# Proiect_OpenBook_V2_v1.net
KiCad netlist of a schematic drawn in EAGLE
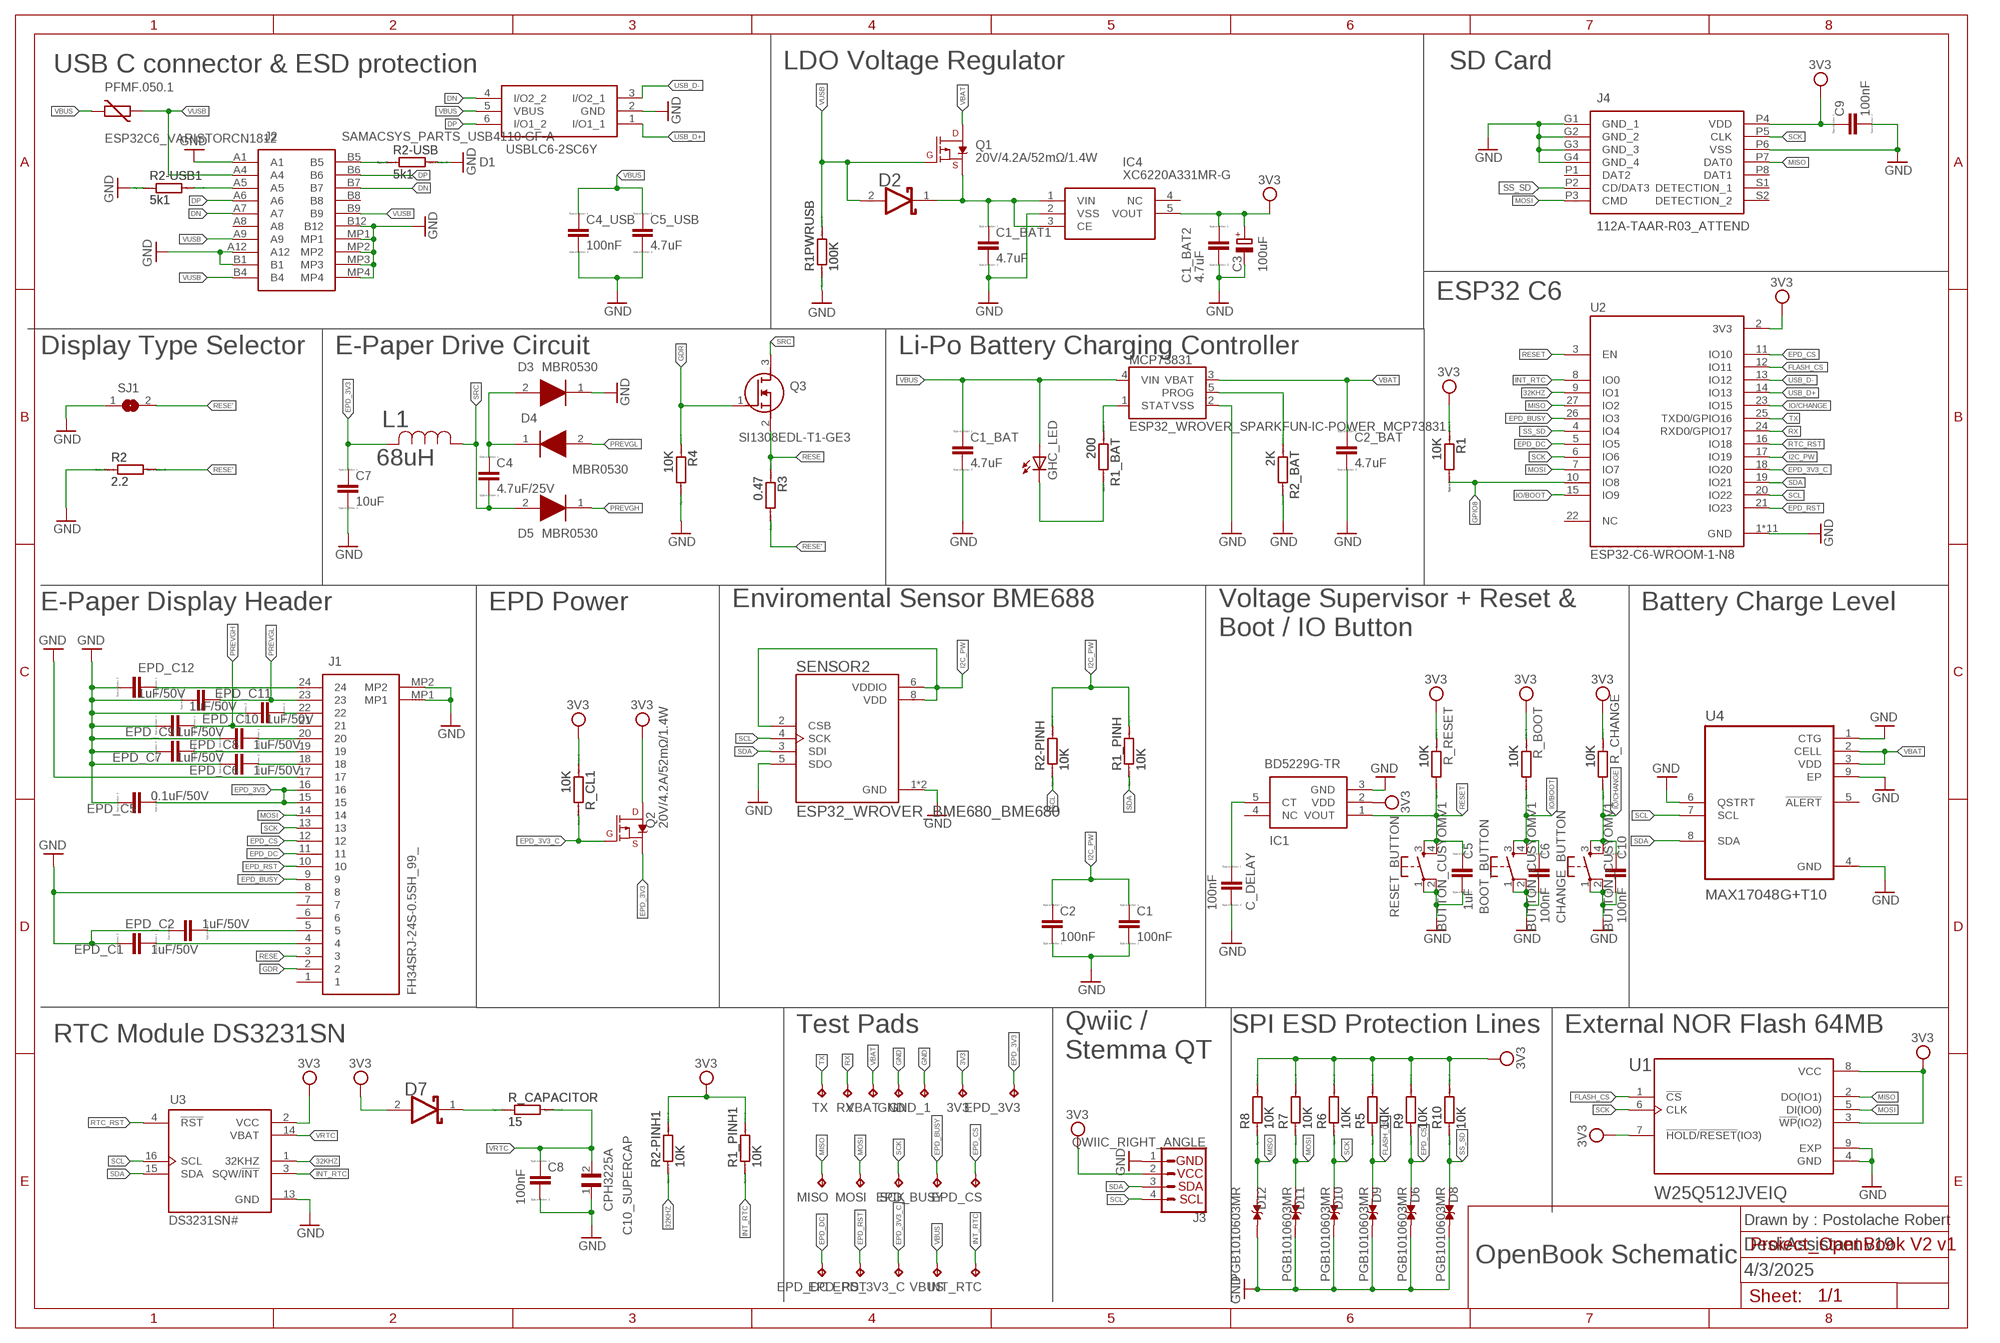
[diagram p0: schematic, sheet 1]

(export (version "E")
  (design (tool "Eeschema 10.0.6"))
  (components
    (comp (ref "3V3")
      (value "TPTP20R")
      (footprint "eagle-import:TP20R")
      (libsource (lib "eagle-import") (part "TPTP20R"))
    )
    (comp (ref "BOOT_BUTTON")
      (value "BUTTON_CUSYOMV1")
      (footprint "eagle-import:MYBUTTON")
      (libsource (lib "eagle-import") (part "BUTTON_CUSYOMV1"))
    )
    (comp (ref "C1")
      (value "100nF")
      (footprint "eagle-import:ESP32_WROVER_EAGLE-LTSPICE_C0402")
      (libsource (lib "eagle-import") (part "EAGLE-LTSPICE_CC0402"))
    )
    (comp (ref "C1_BAT")
      (value "4.7uF")
      (footprint "eagle-import:ESP32_WROVER_EAGLE-LTSPICE_C0402")
      (libsource (lib "eagle-import") (part "EAGLE-LTSPICE_CC0402"))
    )
    (comp (ref "C1_BAT1")
      (value "4.7uF")
      (footprint "eagle-import:ESP32_WROVER_EAGLE-LTSPICE_C0402")
      (libsource (lib "eagle-import") (part "EAGLE-LTSPICE_CC0402"))
    )
    (comp (ref "C1_BAT2")
      (value "4.7uF")
      (footprint "eagle-import:ESP32_WROVER_EAGLE-LTSPICE_C0402")
      (libsource (lib "eagle-import") (part "EAGLE-LTSPICE_CC0402"))
    )
    (comp (ref "C2")
      (value "100nF")
      (footprint "eagle-import:ESP32_WROVER_EAGLE-LTSPICE_C0402")
      (libsource (lib "eagle-import") (part "EAGLE-LTSPICE_CC0402"))
    )
    (comp (ref "C2_BAT")
      (value "4.7uF")
      (footprint "eagle-import:ESP32_WROVER_EAGLE-LTSPICE_C0402")
      (libsource (lib "eagle-import") (part "EAGLE-LTSPICE_CC0402"))
    )
    (comp (ref "C3")
      (value "100uF")
      (footprint "eagle-import:RCL_CT3528")
      (libsource (lib "eagle-import") (part "RCL_CPOL-EUCT3528"))
    )
    (comp (ref "C4")
      (value "4.7uF/25V")
      (footprint "eagle-import:ESP32_WROVER_EAGLE-LTSPICE_C0402")
      (libsource (lib "eagle-import") (part "EAGLE-LTSPICE_CC0402"))
    )
    (comp (ref "C4_USB")
      (value "100nF")
      (footprint "eagle-import:ESP32_WROVER_EAGLE-LTSPICE_C0402")
      (libsource (lib "eagle-import") (part "EAGLE-LTSPICE_CC0402"))
    )
    (comp (ref "C5")
      (value "1uF")
      (footprint "eagle-import:ESP32_WROVER_EAGLE-LTSPICE_C0402")
      (libsource (lib "eagle-import") (part "EAGLE-LTSPICE_CC0402"))
    )
    (comp (ref "C5_USB")
      (value "4.7uF")
      (footprint "eagle-import:ESP32_WROVER_EAGLE-LTSPICE_C0402")
      (libsource (lib "eagle-import") (part "EAGLE-LTSPICE_CC0402"))
    )
    (comp (ref "C6")
      (value "100nF")
      (footprint "eagle-import:ESP32_WROVER_EAGLE-LTSPICE_C0402")
      (libsource (lib "eagle-import") (part "EAGLE-LTSPICE_CC0402"))
    )
    (comp (ref "C7")
      (value "10uF")
      (footprint "eagle-import:ESP32_WROVER_EAGLE-LTSPICE_C0402")
      (libsource (lib "eagle-import") (part "EAGLE-LTSPICE_CC0402"))
    )
    (comp (ref "C8")
      (value "100nF")
      (footprint "eagle-import:ESP32_WROVER_EAGLE-LTSPICE_C0402")
      (libsource (lib "eagle-import") (part "EAGLE-LTSPICE_CC0402"))
    )
    (comp (ref "C9")
      (value "100nF")
      (footprint "eagle-import:ESP32_WROVER_EAGLE-LTSPICE_C0402")
      (libsource (lib "eagle-import") (part "EAGLE-LTSPICE_CC0402"))
    )
    (comp (ref "C10")
      (value "100nF")
      (footprint "eagle-import:ESP32_WROVER_EAGLE-LTSPICE_C0402")
      (libsource (lib "eagle-import") (part "EAGLE-LTSPICE_CC0402"))
    )
    (comp (ref "C10_SUPERCAP")
      (value "CPH3225A")
      (footprint "eagle-import:CAPCP3225X100N")
      (fields (field (name "MF") "Seiko Instruments"))
      (libsource (lib "eagle-import") (part "CPH3225A"))
    )
    (comp (ref "CHANGE_BUTTON")
      (value "BUTTON_CUSYOMV1")
      (footprint "eagle-import:MYBUTTON")
      (libsource (lib "eagle-import") (part "BUTTON_CUSYOMV1"))
    )
    (comp (ref "C_DELAY")
      (value "100nF")
      (footprint "eagle-import:ESP32_WROVER_EAGLE-LTSPICE_C0402")
      (libsource (lib "eagle-import") (part "EAGLE-LTSPICE_CC0402"))
    )
    (comp (ref "D1")
      (value "USBLC6-2SC6Y")
      (footprint "eagle-import:SOT95P280X145-6N")
      (fields (field (name "MF") "STMicroelectronics"))
      (libsource (lib "eagle-import") (part "USBLC6-2SC6Y"))
    )
    (comp (ref "D2")
      (value "ESP32_WROVER_AVX---SD0805S020S1R0_AVX_SD0805S020S1R0_0_0AVX_SD0805S020S1R0_0_0")
      (footprint "eagle-import:ESP32_WROVER_AVX---SD0805S020S1R0_AVX_SD0805S020S1R0_0")
      (fields
        (field (name "DIGIKEY_PART_NUMBER") "478-7800-1-ND")
        (field (name "MF") "AVX")
        (field (name "MOUSER_PART_NUMBER") "581-SD0805S020S1R0")
      )
      (libsource (lib "eagle-import") (part "ESP32_WROVER_AVX---SD0805S020S1R0_AVX_SD0805S020S1R0_0_0AVX_SD0805S020S1R0_0_0"))
    )
    (comp (ref "D3")
      (value "MBR0530")
      (footprint "eagle-import:SOD3716X135N")
      (fields (field (name "MF") "ON Semiconductor"))
      (libsource (lib "eagle-import") (part "MBR0530"))
    )
    (comp (ref "D4")
      (value "MBR0530")
      (footprint "eagle-import:SOD3716X135N")
      (fields (field (name "MF") "ON Semiconductor"))
      (libsource (lib "eagle-import") (part "MBR0530"))
    )
    (comp (ref "D5")
      (value "MBR0530")
      (footprint "eagle-import:SOD3716X135N")
      (fields (field (name "MF") "ON Semiconductor"))
      (libsource (lib "eagle-import") (part "MBR0530"))
    )
    (comp (ref "D6")
      (value "PGB1010603MR")
      (footprint "eagle-import:DIOC1608X36N")
      (fields (field (name "MF") "Littelfuse Inc."))
      (libsource (lib "eagle-import") (part "PGB1010603MR"))
    )
    (comp (ref "D7")
      (value "ESP32_WROVER_AVX---SD0805S020S1R0_AVX_SD0805S020S1R0_0_0AVX_SD0805S020S1R0_0_0")
      (footprint "eagle-import:ESP32_WROVER_AVX---SD0805S020S1R0_AVX_SD0805S020S1R0_0")
      (fields
        (field (name "DIGIKEY_PART_NUMBER") "478-7800-1-ND")
        (field (name "MF") "AVX")
        (field (name "MOUSER_PART_NUMBER") "581-SD0805S020S1R0")
      )
      (libsource (lib "eagle-import") (part "ESP32_WROVER_AVX---SD0805S020S1R0_AVX_SD0805S020S1R0_0_0AVX_SD0805S020S1R0_0_0"))
    )
    (comp (ref "D8")
      (value "PGB1010603MR")
      (footprint "eagle-import:DIOC1608X36N")
      (fields (field (name "MF") "Littelfuse Inc."))
      (libsource (lib "eagle-import") (part "PGB1010603MR"))
    )
    (comp (ref "D9")
      (value "PGB1010603MR")
      (footprint "eagle-import:DIOC1608X36N")
      (fields (field (name "MF") "Littelfuse Inc."))
      (libsource (lib "eagle-import") (part "PGB1010603MR"))
    )
    (comp (ref "D10")
      (value "PGB1010603MR")
      (footprint "eagle-import:DIOC1608X36N")
      (fields (field (name "MF") "Littelfuse Inc."))
      (libsource (lib "eagle-import") (part "PGB1010603MR"))
    )
    (comp (ref "D11")
      (value "PGB1010603MR")
      (footprint "eagle-import:DIOC1608X36N")
      (fields (field (name "MF") "Littelfuse Inc."))
      (libsource (lib "eagle-import") (part "PGB1010603MR"))
    )
    (comp (ref "D12")
      (value "PGB1010603MR")
      (footprint "eagle-import:DIOC1608X36N")
      (fields (field (name "MF") "Littelfuse Inc."))
      (libsource (lib "eagle-import") (part "PGB1010603MR"))
    )
    (comp (ref "EPD_3V3")
      (value "TPTP20R")
      (footprint "eagle-import:TP20R")
      (libsource (lib "eagle-import") (part "TPTP20R"))
    )
    (comp (ref "EPD_3V3_C")
      (value "TPTP20R")
      (footprint "eagle-import:TP20R")
      (libsource (lib "eagle-import") (part "TPTP20R"))
    )
    (comp (ref "EPD_BUSY")
      (value "TPTP20R")
      (footprint "eagle-import:TP20R")
      (libsource (lib "eagle-import") (part "TPTP20R"))
    )
    (comp (ref "EPD_C1")
      (value "1uF/50V")
      (footprint "eagle-import:ESP32_WROVER_EAGLE-LTSPICE_C0402")
      (libsource (lib "eagle-import") (part "EAGLE-LTSPICE_CC0402"))
    )
    (comp (ref "EPD_C2")
      (value "1uF/50V")
      (footprint "eagle-import:ESP32_WROVER_EAGLE-LTSPICE_C0402")
      (libsource (lib "eagle-import") (part "EAGLE-LTSPICE_CC0402"))
    )
    (comp (ref "EPD_C5")
      (value "0.1uF/50V")
      (footprint "eagle-import:ESP32_WROVER_EAGLE-LTSPICE_C0402")
      (libsource (lib "eagle-import") (part "EAGLE-LTSPICE_CC0402"))
    )
    (comp (ref "EPD_C6")
      (value "1uF/50V")
      (footprint "eagle-import:ESP32_WROVER_EAGLE-LTSPICE_C0402")
      (libsource (lib "eagle-import") (part "EAGLE-LTSPICE_CC0402"))
    )
    (comp (ref "EPD_C7")
      (value "1uF/50V")
      (footprint "eagle-import:ESP32_WROVER_EAGLE-LTSPICE_C0402")
      (libsource (lib "eagle-import") (part "EAGLE-LTSPICE_CC0402"))
    )
    (comp (ref "EPD_C8")
      (value "1uF/50V")
      (footprint "eagle-import:ESP32_WROVER_EAGLE-LTSPICE_C0402")
      (libsource (lib "eagle-import") (part "EAGLE-LTSPICE_CC0402"))
    )
    (comp (ref "EPD_C9")
      (value "1uF/50V")
      (footprint "eagle-import:ESP32_WROVER_EAGLE-LTSPICE_C0402")
      (libsource (lib "eagle-import") (part "EAGLE-LTSPICE_CC0402"))
    )
    (comp (ref "EPD_C10")
      (value "1uF/50V")
      (footprint "eagle-import:ESP32_WROVER_EAGLE-LTSPICE_C0402")
      (libsource (lib "eagle-import") (part "EAGLE-LTSPICE_CC0402"))
    )
    (comp (ref "EPD_C11")
      (value "1uF/50V")
      (footprint "eagle-import:ESP32_WROVER_EAGLE-LTSPICE_C0402")
      (libsource (lib "eagle-import") (part "EAGLE-LTSPICE_CC0402"))
    )
    (comp (ref "EPD_C12")
      (value "1uF/50V")
      (footprint "eagle-import:ESP32_WROVER_EAGLE-LTSPICE_C0402")
      (libsource (lib "eagle-import") (part "EAGLE-LTSPICE_CC0402"))
    )
    (comp (ref "EPD_CS")
      (value "TPTP20R")
      (footprint "eagle-import:TP20R")
      (libsource (lib "eagle-import") (part "TPTP20R"))
    )
    (comp (ref "EPD_DC")
      (value "TPTP20R")
      (footprint "eagle-import:TP20R")
      (libsource (lib "eagle-import") (part "TPTP20R"))
    )
    (comp (ref "EPD_RST")
      (value "TPTP20R")
      (footprint "eagle-import:TP20R")
      (libsource (lib "eagle-import") (part "TPTP20R"))
    )
    (comp (ref "GHC_LED")
      (value "ADAFRUIT_LEDCHIP-LED0603")
      (footprint "eagle-import:ADAFRUIT_CHIP-LED0603")
      (libsource (lib "eagle-import") (part "ADAFRUIT_LEDCHIP-LED0603"))
    )
    (comp (ref "GND")
      (value "TPTP20R")
      (footprint "eagle-import:TP20R")
      (libsource (lib "eagle-import") (part "TPTP20R"))
    )
    (comp (ref "GND_1")
      (value "TPTP20R")
      (footprint "eagle-import:TP20R")
      (libsource (lib "eagle-import") (part "TPTP20R"))
    )
    (comp (ref "IC1")
      (value "BD5229G-TR")
      (footprint "eagle-import:SOT95P280X125-5N")
      (fields (field (name "MOUSER_PART_NUMBER") "755-BD5229G-TR"))
      (libsource (lib "eagle-import") (part "BD5229G-TR"))
    )
    (comp (ref "IC4")
      (value "XC6220A331MR-G")
      (footprint "eagle-import:SOT95P280X120-5N")
      (fields (field (name "MOUSER_PART_NUMBER") "865-XC6220A331MR-G"))
      (libsource (lib "eagle-import") (part "XC6220A331MR-G"))
    )
    (comp (ref "INT_RTC")
      (value "TPTP20R")
      (footprint "eagle-import:TP20R")
      (libsource (lib "eagle-import") (part "TPTP20R"))
    )
    (comp (ref "J1")
      (value "FH34SRJ-24S-0.5SH_99_")
      (footprint "eagle-import:FH34SRJ24S05SH99")
      (fields
        (field (name "MANUFACTURER_PART_NUMBER") "FH34SRJ-24S-0.5SH(99)")
        (field (name "MOUSER_PART_NUMBER") "798-FH34SRJ24S05SH99")
      )
      (libsource (lib "eagle-import") (part "FH34SRJ-24S-0.5SH_99_"))
    )
    (comp (ref "J2")
      (value "SAMACSYS_PARTS_USB4110-GF-A")
      (footprint "eagle-import:SAMACSYS_PARTS_USB4110GFA")
      (fields
        (field (name "MANUFACTURER_PART_NUMBER") "USB4110-GF-A")
        (field (name "MOUSER_PART_NUMBER") "640-USB4110-GF-A")
      )
      (libsource (lib "eagle-import") (part "SAMACSYS_PARTS_USB4110-GF-A"))
    )
    (comp (ref "J3")
      (value "QWIIC_RIGHT_ANGLE")
      (footprint "eagle-import:JST04_1MM_RA")
      (libsource (lib "eagle-import") (part "QWIIC_CONNECTORJS-1MM"))
    )
    (comp (ref "J4")
      (value "112A-TAAR-R03_ATTEND")
      (footprint "eagle-import:112ATAARR03ATTEND")
      (fields (field (name "MANUFACTURER_PART_NUMBER") "112A-TAAR-R03 ATTEND"))
      (libsource (lib "eagle-import") (part "112A-TAAR-R03_ATTEND"))
    )
    (comp (ref "L1")
      (value "68uH")
      (footprint "eagle-import:IND_4828-WE-TPC_WRE")
      (fields
        (field (name "MANUFACTURER_PART_NUMBER") "744043680")
        (field (name "COPYRIGHT") "Copyright (C) 2024 Ultra Librarian. All rights reserved.")
      )
      (libsource (lib "eagle-import") (part "744043680IND_4828-WE-TPC_WRE"))
    )
    (comp (ref "MCP73831")
      (value "ESP32_WROVER_SPARKFUN-IC-POWER_MCP73831")
      (footprint "eagle-import:ESP32_WROVER_SPARKFUN-IC-POWER_SOT23-5")
      (libsource (lib "eagle-import") (part "ESP32_WROVER_SPARKFUN-IC-POWER_MCP73831"))
    )
    (comp (ref "MISO")
      (value "TPTP20R")
      (footprint "eagle-import:TP20R")
      (libsource (lib "eagle-import") (part "TPTP20R"))
    )
    (comp (ref "MOSI")
      (value "TPTP20R")
      (footprint "eagle-import:TP20R")
      (libsource (lib "eagle-import") (part "TPTP20R"))
    )
    (comp (ref "PFMF.050.1")
      (value "ESP32C6_VARISTORCN1812")
      (footprint "eagle-import:ESP32C6_VARISTOR_CT_CN1812")
      (libsource (lib "eagle-import") (part "ESP32C6_VARISTORCN1812"))
    )
    (comp (ref "Q1")
      (value "20V/4.2A/52mΩ/1.4W")
      (footprint "eagle-import:ESP32_WROVER_SPARKFUN-DISCRETESEMI_SOT23-3")
      (libsource (lib "eagle-import") (part "ESP32_WROVER_SPARKFUN-DISCRETESEMI_MOSFET_PCH-DMG2305UX-7"))
    )
    (comp (ref "Q2")
      (value "20V/4.2A/52mΩ/1.4W")
      (footprint "eagle-import:ESP32_WROVER_SPARKFUN-DISCRETESEMI_SOT23-3")
      (libsource (lib "eagle-import") (part "ESP32_WROVER_SPARKFUN-DISCRETESEMI_MOSFET_PCH-DMG2305UX-7"))
    )
    (comp (ref "Q3")
      (value "SI1308EDL-T1-GE3")
      (footprint "eagle-import:SOT65P210X110-3N")
      (fields (field (name "MF") "Vishay Siliconix"))
      (libsource (lib "eagle-import") (part "SI1308EDL-T1-GE3"))
    )
    (comp (ref "R1")
      (value "10K")
      (footprint "eagle-import:ESP32_WROVER_EAGLE-LTSPICE_R0402")
      (libsource (lib "eagle-import") (part "ESP32_WROVER_EAGLE-LTSPICE_RR0402"))
    )
    (comp (ref "R1PWRUSB")
      (value "100K")
      (footprint "eagle-import:ESP32_WROVER_EAGLE-LTSPICE_R0402")
      (libsource (lib "eagle-import") (part "ESP32_WROVER_EAGLE-LTSPICE_RR0402"))
    )
    (comp (ref "R1_BAT")
      (value "200")
      (footprint "eagle-import:ESP32_WROVER_EAGLE-LTSPICE_R0402")
      (libsource (lib "eagle-import") (part "ESP32_WROVER_EAGLE-LTSPICE_RR0402"))
    )
    (comp (ref "R1_PINH")
      (value "10K")
      (footprint "eagle-import:ESP32_WROVER_EAGLE-LTSPICE_R0402")
      (libsource (lib "eagle-import") (part "ESP32_WROVER_EAGLE-LTSPICE_RR0402"))
    )
    (comp (ref "R1_PINH1")
      (value "10K")
      (footprint "eagle-import:ESP32_WROVER_EAGLE-LTSPICE_R0402")
      (libsource (lib "eagle-import") (part "ESP32_WROVER_EAGLE-LTSPICE_RR0402"))
    )
    (comp (ref "R2")
      (value "2.2")
      (footprint "eagle-import:ESP32_WROVER_EAGLE-LTSPICE_R0402")
      (libsource (lib "eagle-import") (part "ESP32_WROVER_EAGLE-LTSPICE_RR0402"))
    )
    (comp (ref "R2-PINH")
      (value "10K")
      (footprint "eagle-import:ESP32_WROVER_EAGLE-LTSPICE_R0402")
      (libsource (lib "eagle-import") (part "ESP32_WROVER_EAGLE-LTSPICE_RR0402"))
    )
    (comp (ref "R2-PINH1")
      (value "10K")
      (footprint "eagle-import:ESP32_WROVER_EAGLE-LTSPICE_R0402")
      (libsource (lib "eagle-import") (part "ESP32_WROVER_EAGLE-LTSPICE_RR0402"))
    )
    (comp (ref "R2-USB")
      (value "5k1")
      (footprint "eagle-import:ESP32_WROVER_EAGLE-LTSPICE_R0402")
      (libsource (lib "eagle-import") (part "ESP32_WROVER_EAGLE-LTSPICE_RR0402"))
    )
    (comp (ref "R2-USB1")
      (value "5k1")
      (footprint "eagle-import:ESP32_WROVER_EAGLE-LTSPICE_R0402")
      (libsource (lib "eagle-import") (part "ESP32_WROVER_EAGLE-LTSPICE_RR0402"))
    )
    (comp (ref "R2_BAT")
      (value "2K")
      (footprint "eagle-import:ESP32_WROVER_EAGLE-LTSPICE_R0402")
      (libsource (lib "eagle-import") (part "ESP32_WROVER_EAGLE-LTSPICE_RR0402"))
    )
    (comp (ref "R3")
      (value "0.47")
      (footprint "eagle-import:ESP32_WROVER_EAGLE-LTSPICE_R0402")
      (libsource (lib "eagle-import") (part "ESP32_WROVER_EAGLE-LTSPICE_RR0402"))
    )
    (comp (ref "R4")
      (value "10K")
      (footprint "eagle-import:ESP32_WROVER_EAGLE-LTSPICE_R0402")
      (libsource (lib "eagle-import") (part "ESP32_WROVER_EAGLE-LTSPICE_RR0402"))
    )
    (comp (ref "R5")
      (value "10K")
      (footprint "eagle-import:ESP32_WROVER_EAGLE-LTSPICE_R0402")
      (libsource (lib "eagle-import") (part "ESP32_WROVER_EAGLE-LTSPICE_RR0402"))
    )
    (comp (ref "R6")
      (value "10K")
      (footprint "eagle-import:ESP32_WROVER_EAGLE-LTSPICE_R0402")
      (libsource (lib "eagle-import") (part "ESP32_WROVER_EAGLE-LTSPICE_RR0402"))
    )
    (comp (ref "R7")
      (value "10K")
      (footprint "eagle-import:ESP32_WROVER_EAGLE-LTSPICE_R0402")
      (libsource (lib "eagle-import") (part "ESP32_WROVER_EAGLE-LTSPICE_RR0402"))
    )
    (comp (ref "R8")
      (value "10K")
      (footprint "eagle-import:ESP32_WROVER_EAGLE-LTSPICE_R0402")
      (libsource (lib "eagle-import") (part "ESP32_WROVER_EAGLE-LTSPICE_RR0402"))
    )
    (comp (ref "R9")
      (value "10K")
      (footprint "eagle-import:ESP32_WROVER_EAGLE-LTSPICE_R0402")
      (libsource (lib "eagle-import") (part "ESP32_WROVER_EAGLE-LTSPICE_RR0402"))
    )
    (comp (ref "R10")
      (value "10K")
      (footprint "eagle-import:ESP32_WROVER_EAGLE-LTSPICE_R0402")
      (libsource (lib "eagle-import") (part "ESP32_WROVER_EAGLE-LTSPICE_RR0402"))
    )
    (comp (ref "RESET_BUTTON")
      (value "BUTTON_CUSYOMV1")
      (footprint "eagle-import:MYBUTTON")
      (libsource (lib "eagle-import") (part "BUTTON_CUSYOMV1"))
    )
    (comp (ref "RX")
      (value "TPTP20R")
      (footprint "eagle-import:TP20R")
      (libsource (lib "eagle-import") (part "TPTP20R"))
    )
    (comp (ref "R_BOOT")
      (value "10K")
      (footprint "eagle-import:ESP32_WROVER_EAGLE-LTSPICE_R0402")
      (libsource (lib "eagle-import") (part "ESP32_WROVER_EAGLE-LTSPICE_RR0402"))
    )
    (comp (ref "R_CAPACITOR")
      (value "15")
      (footprint "eagle-import:ESP32_WROVER_EAGLE-LTSPICE_R0402")
      (libsource (lib "eagle-import") (part "ESP32_WROVER_EAGLE-LTSPICE_RR0402"))
    )
    (comp (ref "R_CHANGE")
      (value "10K")
      (footprint "eagle-import:ESP32_WROVER_EAGLE-LTSPICE_R0402")
      (libsource (lib "eagle-import") (part "ESP32_WROVER_EAGLE-LTSPICE_RR0402"))
    )
    (comp (ref "R_CL1")
      (value "10K")
      (footprint "eagle-import:ESP32_WROVER_EAGLE-LTSPICE_R0402")
      (libsource (lib "eagle-import") (part "ESP32_WROVER_EAGLE-LTSPICE_RR0402"))
    )
    (comp (ref "R_RESET")
      (value "10K")
      (footprint "eagle-import:ESP32_WROVER_EAGLE-LTSPICE_R0402")
      (libsource (lib "eagle-import") (part "ESP32_WROVER_EAGLE-LTSPICE_RR0402"))
    )
    (comp (ref "SCK")
      (value "TPTP20R")
      (footprint "eagle-import:TP20R")
      (libsource (lib "eagle-import") (part "TPTP20R"))
    )
    (comp (ref "SENSOR2")
      (value "ESP32_WROVER_BME680_BME680")
      (footprint "eagle-import:ESP32_WROVER_BME680_PSON80P300X300X100-8N")
      (fields (field (name "MF") "Bosch Sensortec") (field (name "MP") "BME680"))
      (libsource (lib "eagle-import") (part "ESP32_WROVER_BME680_BME680"))
    )
    (comp (ref "SJ1") (value "SJ") (footprint "eagle-import:SJ") (libsource (lib "eagle-import") (part "SJ")))
    (comp (ref "TX")
      (value "TPTP20R")
      (footprint "eagle-import:TP20R")
      (libsource (lib "eagle-import") (part "TPTP20R"))
    )
    (comp (ref "U1")
      (value "W25Q512JVEIQ")
      (footprint "eagle-import:SON127P600X800X80-9N")
      (fields (field (name "MF") "Winbond Electronics"))
      (libsource (lib "eagle-import") (part "W25Q512JVEIQ"))
    )
    (comp (ref "U2")
      (value "ESP32-C6-WROOM-1-N8")
      (footprint "eagle-import:XCVR_ESP32-C6-WROOM-1-N8")
      (fields (field (name "MF") "Espressif Systems"))
      (libsource (lib "eagle-import") (part "ESP32-C6-WROOM-1-N8"))
    )
    (comp (ref "U3")
      (value "DS3231SN#")
      (footprint "eagle-import:SOIC127P1032X265-16N")
      (fields (field (name "MF") "Analog Devices"))
      (libsource (lib "eagle-import") (part "DS3231SN#"))
    )
    (comp (ref "U4")
      (value "MAX17048G+T10")
      (footprint "eagle-import:SON50P200X200X80-9N")
      (fields (field (name "MF") "Analog Devices"))
      (libsource (lib "eagle-import") (part "MAX17048G+T10"))
    )
    (comp (ref "VBAT")
      (value "TPTP20R")
      (footprint "eagle-import:TP20R")
      (libsource (lib "eagle-import") (part "TPTP20R"))
    )
    (comp (ref "VBUS")
      (value "TPTP20R")
      (footprint "eagle-import:TP20R")
      (libsource (lib "eagle-import") (part "TPTP20R"))
    )
  )
  (nets
    (net (code "1") (name "3V3") (class "Default")
      (node (ref "3V3") (pin "TP") (pinfunction "TP_TP") (pintype "input"))
      (node (ref "C1_BAT2") (pin "1") (pinfunction "1_1") (pintype "passive"))
      (node (ref "C3") (pin "+") (pinfunction "+_+") (pintype "passive"))
      (node (ref "C9") (pin "1") (pinfunction "1_1") (pintype "passive"))
      (node (ref "D7") (pin "2") (pinfunction "ANODE_2") (pintype "bidirectional"))
      (node (ref "IC1") (pin "2") (pinfunction "VDD_2") (pintype "bidirectional"))
      (node (ref "IC4") (pin "5") (pinfunction "VOUT_5") (pintype "bidirectional"))
      (node (ref "J3") (pin "2") (pinfunction "2_2") (pintype "power_in"))
      (node (ref "J4") (pin "P4") (pinfunction "VDD_P4") (pintype "bidirectional"))
      (node (ref "Q2") (pin "3") (pinfunction "D_3") (pintype "bidirectional"))
      (node (ref "R1") (pin "1") (pinfunction "1_1") (pintype "passive"))
      (node (ref "R10") (pin "2") (pinfunction "2_2") (pintype "passive"))
      (node (ref "R1_PINH1") (pin "2") (pinfunction "2_2") (pintype "passive"))
      (node (ref "R2-PINH1") (pin "2") (pinfunction "2_2") (pintype "passive"))
      (node (ref "R5") (pin "2") (pinfunction "2_2") (pintype "passive"))
      (node (ref "R6") (pin "2") (pinfunction "2_2") (pintype "passive"))
      (node (ref "R7") (pin "2") (pinfunction "2_2") (pintype "passive"))
      (node (ref "R8") (pin "2") (pinfunction "2_2") (pintype "passive"))
      (node (ref "R9") (pin "2") (pinfunction "2_2") (pintype "passive"))
      (node (ref "R_BOOT") (pin "1") (pinfunction "1_1") (pintype "passive"))
      (node (ref "R_CHANGE") (pin "1") (pinfunction "1_1") (pintype "passive"))
      (node (ref "R_CL1") (pin "1") (pinfunction "1_1") (pintype "passive"))
      (node (ref "R_RESET") (pin "1") (pinfunction "1_1") (pintype "passive"))
      (node (ref "U1") (pin "3") (pinfunction "~{WP}(IO2)_3") (pintype "bidirectional"))
      (node (ref "U1") (pin "7") (pinfunction "~{HOLD}/~{RESET}(IO3)_7") (pintype "bidirectional"))
      (node (ref "U1") (pin "8") (pinfunction "VCC_8") (pintype "power_in"))
      (node (ref "U2") (pin "2") (pinfunction "3V3_2") (pintype "power_in"))
      (node (ref "U3") (pin "2") (pinfunction "VCC_2") (pintype "power_in"))
    )
    (net (code "2") (name "32KHZ") (class "Default")
      (node (ref "R2-PINH1") (pin "1") (pinfunction "1_1") (pintype "passive"))
      (node (ref "U2") (pin "9") (pinfunction "IO1_9") (pintype "bidirectional"))
      (node (ref "U3") (pin "1") (pinfunction "32KHZ_1") (pintype "output"))
    )
    (net (code "3") (name "DN") (class "Default")
      (node (ref "D1") (pin "4") (pinfunction "I/O2_2_4") (pintype "bidirectional"))
      (node (ref "J2") (pin "A7") (pinfunction "A7_A7") (pintype "bidirectional"))
      (node (ref "J2") (pin "B7") (pinfunction "B7_B7") (pintype "bidirectional"))
    )
    (net (code "4") (name "DP") (class "Default")
      (node (ref "D1") (pin "6") (pinfunction "I/O1_2_6") (pintype "bidirectional"))
      (node (ref "J2") (pin "A6") (pinfunction "A6_A6") (pintype "bidirectional"))
      (node (ref "J2") (pin "B6") (pinfunction "B6_B6") (pintype "bidirectional"))
    )
    (net (code "5") (name "EPD_3V3") (class "Default")
      (node (ref "C7") (pin "1") (pinfunction "1_1") (pintype "passive"))
      (node (ref "EPD_3V3") (pin "TP") (pinfunction "TP_TP") (pintype "input"))
      (node (ref "EPD_C5") (pin "1") (pinfunction "1_1") (pintype "passive"))
      (node (ref "J1") (pin "15") (pinfunction "15_15") (pintype "bidirectional"))
      (node (ref "J1") (pin "16") (pinfunction "16_16") (pintype "bidirectional"))
      (node (ref "L1") (pin "2") (pinfunction "2_2") (pintype "passive"))
      (node (ref "Q2") (pin "2") (pinfunction "S_2") (pintype "bidirectional"))
    )
    (net (code "6") (name "EPD_3V3_C") (class "Default")
      (node (ref "EPD_3V3_C") (pin "TP") (pinfunction "TP_TP") (pintype "input"))
      (node (ref "Q2") (pin "1") (pinfunction "G_1") (pintype "bidirectional"))
      (node (ref "R_CL1") (pin "2") (pinfunction "2_2") (pintype "passive"))
      (node (ref "U2") (pin "18") (pinfunction "IO20_18") (pintype "bidirectional"))
    )
    (net (code "7") (name "EPD_BUSY") (class "Default")
      (node (ref "EPD_BUSY") (pin "TP") (pinfunction "TP_TP") (pintype "input"))
      (node (ref "J1") (pin "9") (pinfunction "9_9") (pintype "bidirectional"))
      (node (ref "U2") (pin "26") (pinfunction "IO3_26") (pintype "bidirectional"))
    )
    (net (code "8") (name "EPD_CS") (class "Default")
      (node (ref "D6") (pin "1") (pinfunction "1_1") (pintype "passive"))
      (node (ref "EPD_CS") (pin "TP") (pinfunction "TP_TP") (pintype "input"))
      (node (ref "J1") (pin "12") (pinfunction "12_12") (pintype "bidirectional"))
      (node (ref "R9") (pin "1") (pinfunction "1_1") (pintype "passive"))
      (node (ref "U2") (pin "11") (pinfunction "IO10_11") (pintype "bidirectional"))
    )
    (net (code "9") (name "EPD_DC") (class "Default")
      (node (ref "EPD_DC") (pin "TP") (pinfunction "TP_TP") (pintype "input"))
      (node (ref "J1") (pin "11") (pinfunction "11_11") (pintype "bidirectional"))
      (node (ref "U2") (pin "5") (pinfunction "IO5_5") (pintype "bidirectional"))
    )
    (net (code "10") (name "EPD_RST") (class "Default")
      (node (ref "EPD_RST") (pin "TP") (pinfunction "TP_TP") (pintype "input"))
      (node (ref "J1") (pin "10") (pinfunction "10_10") (pintype "bidirectional"))
      (node (ref "U2") (pin "21") (pinfunction "IO23_21") (pintype "bidirectional"))
    )
    (net (code "11") (name "FLASH_CS") (class "Default")
      (node (ref "D9") (pin "1") (pinfunction "1_1") (pintype "passive"))
      (node (ref "R5") (pin "1") (pinfunction "1_1") (pintype "passive"))
      (node (ref "U1") (pin "1") (pinfunction "~{CS}_1") (pintype "input"))
      (node (ref "U2") (pin "12") (pinfunction "IO11_12") (pintype "bidirectional"))
    )
    (net (code "12") (name "GDR") (class "Default")
      (node (ref "J1") (pin "2") (pinfunction "2_2") (pintype "bidirectional"))
      (node (ref "Q3") (pin "1") (pinfunction "G_1") (pintype "bidirectional"))
      (node (ref "R4") (pin "1") (pinfunction "1_1") (pintype "passive"))
    )
    (net (code "13") (name "GND") (class "Default")
      (node (ref "BOOT_BUTTON") (pin "1") (pinfunction "1_1") (pintype "passive"))
      (node (ref "BOOT_BUTTON") (pin "2") (pinfunction "2_2") (pintype "passive"))
      (node (ref "C1") (pin "2") (pinfunction "2_2") (pintype "passive"))
      (node (ref "C10") (pin "2") (pinfunction "2_2") (pintype "passive"))
      (node (ref "C10_SUPERCAP") (pin "1") (pinfunction "1_1") (pintype "passive"))
      (node (ref "C1_BAT") (pin "2") (pinfunction "2_2") (pintype "passive"))
      (node (ref "C1_BAT1") (pin "2") (pinfunction "2_2") (pintype "passive"))
      (node (ref "C1_BAT2") (pin "2") (pinfunction "2_2") (pintype "passive"))
      (node (ref "C2") (pin "2") (pinfunction "2_2") (pintype "passive"))
      (node (ref "C2_BAT") (pin "2") (pinfunction "2_2") (pintype "passive"))
      (node (ref "C3") (pin "-") (pinfunction "-_-") (pintype "passive"))
      (node (ref "C4_USB") (pin "2") (pinfunction "2_2") (pintype "passive"))
      (node (ref "C5") (pin "2") (pinfunction "2_2") (pintype "passive"))
      (node (ref "C5_USB") (pin "2") (pinfunction "2_2") (pintype "passive"))
      (node (ref "C6") (pin "2") (pinfunction "2_2") (pintype "passive"))
      (node (ref "C7") (pin "2") (pinfunction "2_2") (pintype "passive"))
      (node (ref "C8") (pin "2") (pinfunction "2_2") (pintype "passive"))
      (node (ref "C9") (pin "2") (pinfunction "2_2") (pintype "passive"))
      (node (ref "CHANGE_BUTTON") (pin "1") (pinfunction "1_1") (pintype "passive"))
      (node (ref "CHANGE_BUTTON") (pin "2") (pinfunction "2_2") (pintype "passive"))
      (node (ref "C_DELAY") (pin "2") (pinfunction "2_2") (pintype "passive"))
      (node (ref "D1") (pin "2") (pinfunction "GND_2") (pintype "bidirectional"))
      (node (ref "D10") (pin "2") (pinfunction "2_2") (pintype "passive"))
      (node (ref "D11") (pin "2") (pinfunction "2_2") (pintype "passive"))
      (node (ref "D12") (pin "2") (pinfunction "2_2") (pintype "passive"))
      (node (ref "D3") (pin "1") (pinfunction "K_1") (pintype "bidirectional"))
      (node (ref "D6") (pin "2") (pinfunction "2_2") (pintype "passive"))
      (node (ref "D8") (pin "2") (pinfunction "2_2") (pintype "passive"))
      (node (ref "D9") (pin "2") (pinfunction "2_2") (pintype "passive"))
      (node (ref "EPD_C1") (pin "2") (pinfunction "2_2") (pintype "passive"))
      (node (ref "EPD_C10") (pin "2") (pinfunction "2_2") (pintype "passive"))
      (node (ref "EPD_C11") (pin "2") (pinfunction "2_2") (pintype "passive"))
      (node (ref "EPD_C12") (pin "2") (pinfunction "2_2") (pintype "passive"))
      (node (ref "EPD_C2") (pin "2") (pinfunction "2_2") (pintype "passive"))
      (node (ref "EPD_C5") (pin "2") (pinfunction "2_2") (pintype "passive"))
      (node (ref "EPD_C6") (pin "2") (pinfunction "2_2") (pintype "passive"))
      (node (ref "EPD_C7") (pin "2") (pinfunction "2_2") (pintype "passive"))
      (node (ref "EPD_C8") (pin "2") (pinfunction "2_2") (pintype "passive"))
      (node (ref "EPD_C9") (pin "2") (pinfunction "2_2") (pintype "passive"))
      (node (ref "GND") (pin "TP") (pinfunction "TP_TP") (pintype "input"))
      (node (ref "GND_1") (pin "TP") (pinfunction "TP_TP") (pintype "input"))
      (node (ref "IC1") (pin "3") (pinfunction "GND_3") (pintype "bidirectional"))
      (node (ref "IC4") (pin "2") (pinfunction "VSS_2") (pintype "bidirectional"))
      (node (ref "J1") (pin "17") (pinfunction "17_17") (pintype "bidirectional"))
      (node (ref "J1") (pin "8") (pinfunction "8_8") (pintype "bidirectional"))
      (node (ref "J1") (pin "MP1") (pinfunction "MP1_MP1") (pintype "bidirectional"))
      (node (ref "J1") (pin "MP2") (pinfunction "MP2_MP2") (pintype "bidirectional"))
      (node (ref "J2") (pin "A1") (pinfunction "A1_A1") (pintype "bidirectional"))
      (node (ref "J2") (pin "A12") (pinfunction "A12_A12") (pintype "bidirectional"))
      (node (ref "J2") (pin "B1") (pinfunction "B1_B1") (pintype "bidirectional"))
      (node (ref "J2") (pin "B12") (pinfunction "B12_B12") (pintype "bidirectional"))
      (node (ref "J2") (pin "MP1") (pinfunction "MP1_MP1") (pintype "bidirectional"))
      (node (ref "J2") (pin "MP2") (pinfunction "MP2_MP2") (pintype "bidirectional"))
      (node (ref "J2") (pin "MP3") (pinfunction "MP3_MP3") (pintype "bidirectional"))
      (node (ref "J2") (pin "MP4") (pinfunction "MP4_MP4") (pintype "bidirectional"))
      (node (ref "J3") (pin "1") (pinfunction "1_1") (pintype "power_in"))
      (node (ref "J4") (pin "G1") (pinfunction "GND_1_G1") (pintype "bidirectional"))
      (node (ref "J4") (pin "G2") (pinfunction "GND_2_G2") (pintype "bidirectional"))
      (node (ref "J4") (pin "G3") (pinfunction "GND_3_G3") (pintype "bidirectional"))
      (node (ref "J4") (pin "G4") (pinfunction "GND_4_G4") (pintype "bidirectional"))
      (node (ref "J4") (pin "P6") (pinfunction "VSS_P6") (pintype "bidirectional"))
      (node (ref "MCP73831") (pin "2") (pinfunction "VSS_2") (pintype "power_in"))
      (node (ref "R1PWRUSB") (pin "1") (pinfunction "1_1") (pintype "passive"))
      (node (ref "R2") (pin "1") (pinfunction "1_1") (pintype "passive"))
      (node (ref "R2-USB") (pin "2") (pinfunction "2_2") (pintype "passive"))
      (node (ref "R2-USB1") (pin "1") (pinfunction "1_1") (pintype "passive"))
      (node (ref "R2_BAT") (pin "2") (pinfunction "2_2") (pintype "passive"))
      (node (ref "R4") (pin "2") (pinfunction "2_2") (pintype "passive"))
      (node (ref "RESET_BUTTON") (pin "1") (pinfunction "1_1") (pintype "passive"))
      (node (ref "RESET_BUTTON") (pin "2") (pinfunction "2_2") (pintype "passive"))
      (node (ref "SENSOR2") (pin "1") (pinfunction "GND_1") (pintype "power_in"))
      (node (ref "SENSOR2") (pin "5") (pinfunction "SDO_5") (pintype "bidirectional"))
      (node (ref "SENSOR2") (pin "7") (pinfunction "GND_7") (pintype "power_in"))
      (node (ref "SJ1") (pin "1") (pinfunction "1_1") (pintype "passive"))
      (node (ref "U1") (pin "4") (pinfunction "GND_4") (pintype "power_in"))
      (node (ref "U1") (pin "9") (pinfunction "EXP_9") (pintype "passive"))
      (node (ref "U2") (pin "1") (pinfunction "GND_1") (pintype "power_in"))
      (node (ref "U2") (pin "28") (pinfunction "GND_28") (pintype "power_in"))
      (node (ref "U2") (pin "29_1") (pinfunction "GND_29_1") (pintype "power_in"))
      (node (ref "U2") (pin "29_2") (pinfunction "GND_29_2") (pintype "power_in"))
      (node (ref "U2") (pin "29_3") (pinfunction "GND_29_3") (pintype "power_in"))
      (node (ref "U2") (pin "29_4") (pinfunction "GND_29_4") (pintype "power_in"))
      (node (ref "U2") (pin "29_5") (pinfunction "GND_29_5") (pintype "power_in"))
      (node (ref "U2") (pin "29_6") (pinfunction "GND_29_6") (pintype "power_in"))
      (node (ref "U2") (pin "29_7") (pinfunction "GND_29_7") (pintype "power_in"))
      (node (ref "U2") (pin "29_8") (pinfunction "GND_29_8") (pintype "power_in"))
      (node (ref "U2") (pin "29_9") (pinfunction "GND_29_9") (pintype "power_in"))
      (node (ref "U3") (pin "13") (pinfunction "GND_13") (pintype "power_in"))
      (node (ref "U4") (pin "1") (pinfunction "CTG_1") (pintype "power_in"))
      (node (ref "U4") (pin "4") (pinfunction "GND_4") (pintype "power_in"))
      (node (ref "U4") (pin "6") (pinfunction "QSTRT_6") (pintype "input"))
      (node (ref "U4") (pin "9") (pinfunction "EP_9") (pintype "power_in"))
    )
    (net (code "14") (name "GPIO8") (class "Default")
      (node (ref "R1") (pin "2") (pinfunction "2_2") (pintype "passive"))
      (node (ref "U2") (pin "10") (pinfunction "IO8_10") (pintype "bidirectional"))
    )
    (net (code "15") (name "I2C_PW") (class "Default")
      (node (ref "C1") (pin "1") (pinfunction "1_1") (pintype "passive"))
      (node (ref "C2") (pin "1") (pinfunction "1_1") (pintype "passive"))
      (node (ref "R1_PINH") (pin "2") (pinfunction "2_2") (pintype "passive"))
      (node (ref "R2-PINH") (pin "2") (pinfunction "2_2") (pintype "passive"))
      (node (ref "SENSOR2") (pin "2") (pinfunction "CSB_2") (pintype "input"))
      (node (ref "SENSOR2") (pin "6") (pinfunction "VDDIO_6") (pintype "power_in"))
      (node (ref "SENSOR2") (pin "8") (pinfunction "VDD_8") (pintype "power_in"))
      (node (ref "U2") (pin "17") (pinfunction "IO19_17") (pintype "bidirectional"))
    )
    (net (code "16") (name "INT_RTC") (class "Default")
      (node (ref "INT_RTC") (pin "TP") (pinfunction "TP_TP") (pintype "input"))
      (node (ref "R1_PINH1") (pin "1") (pinfunction "1_1") (pintype "passive"))
      (node (ref "U2") (pin "8") (pinfunction "IO0_8") (pintype "bidirectional"))
      (node (ref "U3") (pin "3") (pinfunction "SQW/~{INT}_3") (pintype "output"))
    )
    (net (code "17") (name "IO{slash}BOOT") (class "Default")
      (node (ref "BOOT_BUTTON") (pin "3") (pinfunction "3_3") (pintype "passive"))
      (node (ref "BOOT_BUTTON") (pin "4") (pinfunction "4_4") (pintype "passive"))
      (node (ref "C6") (pin "1") (pinfunction "1_1") (pintype "passive"))
      (node (ref "R_BOOT") (pin "2") (pinfunction "2_2") (pintype "passive"))
      (node (ref "U2") (pin "15") (pinfunction "IO9_15") (pintype "bidirectional"))
    )
    (net (code "18") (name "IO{slash}CHANGE") (class "Default")
      (node (ref "C10") (pin "1") (pinfunction "1_1") (pintype "passive"))
      (node (ref "CHANGE_BUTTON") (pin "3") (pinfunction "3_3") (pintype "passive"))
      (node (ref "CHANGE_BUTTON") (pin "4") (pinfunction "4_4") (pintype "passive"))
      (node (ref "R_CHANGE") (pin "2") (pinfunction "2_2") (pintype "passive"))
      (node (ref "U2") (pin "23") (pinfunction "IO15_23") (pintype "bidirectional"))
    )
    (net (code "19") (name "MISO") (class "Default")
      (node (ref "D12") (pin "1") (pinfunction "1_1") (pintype "passive"))
      (node (ref "J4") (pin "P7") (pinfunction "DAT0_P7") (pintype "bidirectional"))
      (node (ref "MISO") (pin "TP") (pinfunction "TP_TP") (pintype "input"))
      (node (ref "R8") (pin "1") (pinfunction "1_1") (pintype "passive"))
      (node (ref "U1") (pin "2") (pinfunction "DO(IO1)_2") (pintype "bidirectional"))
      (node (ref "U2") (pin "27") (pinfunction "IO2_27") (pintype "bidirectional"))
    )
    (net (code "20") (name "MOSI") (class "Default")
      (node (ref "D11") (pin "1") (pinfunction "1_1") (pintype "passive"))
      (node (ref "J1") (pin "14") (pinfunction "14_14") (pintype "bidirectional"))
      (node (ref "J4") (pin "P3") (pinfunction "CMD_P3") (pintype "bidirectional"))
      (node (ref "MOSI") (pin "TP") (pinfunction "TP_TP") (pintype "input"))
      (node (ref "R7") (pin "1") (pinfunction "1_1") (pintype "passive"))
      (node (ref "U1") (pin "5") (pinfunction "DI(IO0)_5") (pintype "bidirectional"))
      (node (ref "U2") (pin "7") (pinfunction "IO7_7") (pintype "bidirectional"))
    )
    (net (code "21") (name "Net-(D2-CATHODE)") (class "Default")
      (node (ref "C1_BAT1") (pin "1") (pinfunction "1_1") (pintype "passive"))
      (node (ref "D2") (pin "1") (pinfunction "CATHODE_1") (pintype "bidirectional"))
      (node (ref "IC4") (pin "1") (pinfunction "VIN_1") (pintype "bidirectional"))
      (node (ref "IC4") (pin "3") (pinfunction "CE_3") (pintype "bidirectional"))
      (node (ref "Q1") (pin "2") (pinfunction "S_2") (pintype "bidirectional"))
    )
    (net (code "22") (name "Net-(D3-A)") (class "Default")
      (node (ref "C4") (pin "1") (pinfunction "1_1") (pintype "passive"))
      (node (ref "D3") (pin "2") (pinfunction "A_2") (pintype "bidirectional"))
      (node (ref "D4") (pin "1") (pinfunction "K_1") (pintype "bidirectional"))
    )
    (net (code "23") (name "Net-(D7-CATHODE)") (class "Default")
      (node (ref "D7") (pin "1") (pinfunction "CATHODE_1") (pintype "bidirectional"))
      (node (ref "R_CAPACITOR") (pin "1") (pinfunction "1_1") (pintype "passive"))
    )
    (net (code "24") (name "Net-(EPD_C1-Pad1)") (class "Default")
      (node (ref "EPD_C1") (pin "1") (pinfunction "1_1") (pintype "passive"))
      (node (ref "J1") (pin "4") (pinfunction "4_4") (pintype "bidirectional"))
    )
    (net (code "25") (name "Net-(EPD_C2-Pad1)") (class "Default")
      (node (ref "EPD_C2") (pin "1") (pinfunction "1_1") (pintype "passive"))
      (node (ref "J1") (pin "5") (pinfunction "5_5") (pintype "bidirectional"))
    )
    (net (code "26") (name "Net-(EPD_C6-Pad1)") (class "Default")
      (node (ref "EPD_C6") (pin "1") (pinfunction "1_1") (pintype "passive"))
      (node (ref "J1") (pin "18") (pinfunction "18_18") (pintype "bidirectional"))
    )
    (net (code "27") (name "Net-(EPD_C7-Pad1)") (class "Default")
      (node (ref "EPD_C7") (pin "1") (pinfunction "1_1") (pintype "passive"))
      (node (ref "J1") (pin "19") (pinfunction "19_19") (pintype "bidirectional"))
    )
    (net (code "28") (name "Net-(EPD_C8-Pad1)") (class "Default")
      (node (ref "EPD_C8") (pin "1") (pinfunction "1_1") (pintype "passive"))
      (node (ref "J1") (pin "20") (pinfunction "20_20") (pintype "bidirectional"))
    )
    (net (code "29") (name "Net-(EPD_C10-Pad1)") (class "Default")
      (node (ref "EPD_C10") (pin "1") (pinfunction "1_1") (pintype "passive"))
      (node (ref "J1") (pin "22") (pinfunction "22_22") (pintype "bidirectional"))
    )
    (net (code "30") (name "Net-(EPD_C12-Pad1)") (class "Default")
      (node (ref "EPD_C12") (pin "1") (pinfunction "1_1") (pintype "passive"))
      (node (ref "J1") (pin "24") (pinfunction "24_24") (pintype "bidirectional"))
    )
    (net (code "31") (name "Net-(GHC_LED-PadC)") (class "Default")
      (node (ref "GHC_LED") (pin "C") (pinfunction "C_C") (pintype "passive"))
      (node (ref "R1_BAT") (pin "2") (pinfunction "2_2") (pintype "passive"))
    )
    (net (code "32") (name "Net-(IC1-CT)") (class "Default")
      (node (ref "C_DELAY") (pin "1") (pinfunction "1_1") (pintype "passive"))
      (node (ref "IC1") (pin "5") (pinfunction "CT_5") (pintype "bidirectional"))
    )
    (net (code "33") (name "Net-(J2-PadA5)") (class "Default")
      (node (ref "J2") (pin "A5") (pinfunction "A5_A5") (pintype "bidirectional"))
      (node (ref "R2-USB1") (pin "2") (pinfunction "2_2") (pintype "passive"))
    )
    (net (code "34") (name "Net-(J2-PadB5)") (class "Default")
      (node (ref "J2") (pin "B5") (pinfunction "B5_B5") (pintype "bidirectional"))
      (node (ref "R2-USB") (pin "1") (pinfunction "1_1") (pintype "passive"))
    )
    (net (code "35") (name "Net-(MCP73831-PROG)") (class "Default")
      (node (ref "MCP73831") (pin "5") (pinfunction "PROG_5") (pintype "input"))
      (node (ref "R2_BAT") (pin "1") (pinfunction "1_1") (pintype "passive"))
    )
    (net (code "36") (name "Net-(MCP73831-STAT)") (class "Default")
      (node (ref "MCP73831") (pin "1") (pinfunction "STAT_1") (pintype "output"))
      (node (ref "R1_BAT") (pin "1") (pinfunction "1_1") (pintype "passive"))
    )
    (net (code "37") (name "PREVGH") (class "Default")
      (node (ref "D5") (pin "1") (pinfunction "K_1") (pintype "bidirectional"))
      (node (ref "EPD_C9") (pin "1") (pinfunction "1_1") (pintype "passive"))
      (node (ref "J1") (pin "21") (pinfunction "21_21") (pintype "bidirectional"))
    )
    (net (code "38") (name "PREVGL") (class "Default")
      (node (ref "D4") (pin "2") (pinfunction "A_2") (pintype "bidirectional"))
      (node (ref "EPD_C11") (pin "1") (pinfunction "1_1") (pintype "passive"))
      (node (ref "J1") (pin "23") (pinfunction "23_23") (pintype "bidirectional"))
    )
    (net (code "39") (name "RESE") (class "Default")
      (node (ref "J1") (pin "3") (pinfunction "3_3") (pintype "bidirectional"))
      (node (ref "Q3") (pin "2") (pinfunction "S_2") (pintype "bidirectional"))
      (node (ref "R3") (pin "1") (pinfunction "1_1") (pintype "passive"))
    )
    (net (code "40") (name "RESE'") (class "Default")
      (node (ref "R2") (pin "2") (pinfunction "2_2") (pintype "passive"))
      (node (ref "R3") (pin "2") (pinfunction "2_2") (pintype "passive"))
      (node (ref "SJ1") (pin "2") (pinfunction "2_2") (pintype "passive"))
    )
    (net (code "41") (name "RESET") (class "Default")
      (node (ref "C5") (pin "1") (pinfunction "1_1") (pintype "passive"))
      (node (ref "IC1") (pin "1") (pinfunction "VOUT_1") (pintype "bidirectional"))
      (node (ref "RESET_BUTTON") (pin "3") (pinfunction "3_3") (pintype "passive"))
      (node (ref "RESET_BUTTON") (pin "4") (pinfunction "4_4") (pintype "passive"))
      (node (ref "R_RESET") (pin "2") (pinfunction "2_2") (pintype "passive"))
      (node (ref "U2") (pin "3") (pinfunction "EN_3") (pintype "input"))
    )
    (net (code "42") (name "RTC_RST") (class "Default")
      (node (ref "U2") (pin "16") (pinfunction "IO18_16") (pintype "bidirectional"))
      (node (ref "U3") (pin "4") (pinfunction "~{RST}_4") (pintype "input"))
    )
    (net (code "43") (name "RX") (class "Default")
      (node (ref "RX") (pin "TP") (pinfunction "TP_TP") (pintype "input"))
      (node (ref "U2") (pin "24") (pinfunction "RXD0/GPIO17_24") (pintype "bidirectional"))
    )
    (net (code "44") (name "SCK") (class "Default")
      (node (ref "D10") (pin "1") (pinfunction "1_1") (pintype "passive"))
      (node (ref "J1") (pin "13") (pinfunction "13_13") (pintype "bidirectional"))
      (node (ref "J4") (pin "P5") (pinfunction "CLK_P5") (pintype "bidirectional"))
      (node (ref "R6") (pin "1") (pinfunction "1_1") (pintype "passive"))
      (node (ref "SCK") (pin "TP") (pinfunction "TP_TP") (pintype "input"))
      (node (ref "U1") (pin "6") (pinfunction "CLK_6") (pintype "input"))
      (node (ref "U2") (pin "6") (pinfunction "IO6_6") (pintype "bidirectional"))
    )
    (net (code "45") (name "SCL") (class "Default")
      (node (ref "J3") (pin "4") (pinfunction "4_4") (pintype "passive"))
      (node (ref "R2-PINH") (pin "1") (pinfunction "1_1") (pintype "passive"))
      (node (ref "SENSOR2") (pin "4") (pinfunction "SCK_4") (pintype "input"))
      (node (ref "U2") (pin "20") (pinfunction "IO22_20") (pintype "bidirectional"))
      (node (ref "U3") (pin "16") (pinfunction "SCL_16") (pintype "input"))
      (node (ref "U4") (pin "7") (pinfunction "SCL_7") (pintype "input"))
    )
    (net (code "46") (name "SDA") (class "Default")
      (node (ref "J3") (pin "3") (pinfunction "3_3") (pintype "passive"))
      (node (ref "R1_PINH") (pin "1") (pinfunction "1_1") (pintype "passive"))
      (node (ref "SENSOR2") (pin "3") (pinfunction "SDI_3") (pintype "bidirectional"))
      (node (ref "U2") (pin "19") (pinfunction "IO21_19") (pintype "bidirectional"))
      (node (ref "U3") (pin "15") (pinfunction "SDA_15") (pintype "bidirectional"))
      (node (ref "U4") (pin "8") (pinfunction "SDA_8") (pintype "bidirectional"))
    )
    (net (code "47") (name "SRC") (class "Default")
      (node (ref "C4") (pin "2") (pinfunction "2_2") (pintype "passive"))
      (node (ref "D5") (pin "2") (pinfunction "A_2") (pintype "bidirectional"))
      (node (ref "L1") (pin "1") (pinfunction "1_1") (pintype "passive"))
      (node (ref "Q3") (pin "3") (pinfunction "D_3") (pintype "bidirectional"))
    )
    (net (code "48") (name "SS_SD") (class "Default")
      (node (ref "D8") (pin "1") (pinfunction "1_1") (pintype "passive"))
      (node (ref "J4") (pin "P2") (pinfunction "CD/DAT3_P2") (pintype "bidirectional"))
      (node (ref "R10") (pin "1") (pinfunction "1_1") (pintype "passive"))
      (node (ref "U2") (pin "4") (pinfunction "IO4_4") (pintype "bidirectional"))
    )
    (net (code "49") (name "TX") (class "Default")
      (node (ref "TX") (pin "TP") (pinfunction "TP_TP") (pintype "input"))
      (node (ref "U2") (pin "25") (pinfunction "TXD0/GPIO16_25") (pintype "bidirectional"))
    )
    (net (code "50") (name "USB_D+") (class "Default")
      (node (ref "D1") (pin "1") (pinfunction "I/O1_1_1") (pintype "bidirectional"))
      (node (ref "U2") (pin "14") (pinfunction "IO13_14") (pintype "bidirectional"))
    )
    (net (code "51") (name "USB_D-") (class "Default")
      (node (ref "D1") (pin "3") (pinfunction "I/O2_1_3") (pintype "bidirectional"))
      (node (ref "U2") (pin "13") (pinfunction "IO12_13") (pintype "bidirectional"))
    )
    (net (code "52") (name "VBAT") (class "Default")
      (node (ref "C2_BAT") (pin "1") (pinfunction "1_1") (pintype "passive"))
      (node (ref "MCP73831") (pin "3") (pinfunction "VBAT_3") (pintype "power_in"))
      (node (ref "Q1") (pin "3") (pinfunction "D_3") (pintype "bidirectional"))
      (node (ref "U4") (pin "2") (pinfunction "CELL_2") (pintype "power_in"))
      (node (ref "U4") (pin "3") (pinfunction "VDD_3") (pintype "power_in"))
      (node (ref "VBAT") (pin "TP") (pinfunction "TP_TP") (pintype "input"))
    )
    (net (code "53") (name "VBUS") (class "Default")
      (node (ref "C1_BAT") (pin "1") (pinfunction "1_1") (pintype "passive"))
      (node (ref "C4_USB") (pin "1") (pinfunction "1_1") (pintype "passive"))
      (node (ref "C5_USB") (pin "1") (pinfunction "1_1") (pintype "passive"))
      (node (ref "D1") (pin "5") (pinfunction "VBUS_5") (pintype "bidirectional"))
      (node (ref "GHC_LED") (pin "A") (pinfunction "A_A") (pintype "passive"))
      (node (ref "MCP73831") (pin "4") (pinfunction "VIN_4") (pintype "power_in"))
      (node (ref "PFMF.050.1") (pin "2") (pinfunction "2_2") (pintype "passive"))
      (node (ref "VBUS") (pin "TP") (pinfunction "TP_TP") (pintype "input"))
    )
    (net (code "54") (name "VRTC") (class "Default")
      (node (ref "C10_SUPERCAP") (pin "2") (pinfunction "2_2") (pintype "passive"))
      (node (ref "C8") (pin "1") (pinfunction "1_1") (pintype "passive"))
      (node (ref "R_CAPACITOR") (pin "2") (pinfunction "2_2") (pintype "passive"))
      (node (ref "U3") (pin "14") (pinfunction "VBAT_14") (pintype "power_in"))
    )
    (net (code "55") (name "VUSB") (class "Default")
      (node (ref "D2") (pin "2") (pinfunction "ANODE_2") (pintype "bidirectional"))
      (node (ref "J2") (pin "A4") (pinfunction "A4_A4") (pintype "bidirectional"))
      (node (ref "J2") (pin "A9") (pinfunction "A9_A9") (pintype "bidirectional"))
      (node (ref "J2") (pin "B4") (pinfunction "B4_B4") (pintype "bidirectional"))
      (node (ref "J2") (pin "B9") (pinfunction "B9_B9") (pintype "bidirectional"))
      (node (ref "PFMF.050.1") (pin "1") (pinfunction "1_1") (pintype "passive"))
      (node (ref "Q1") (pin "1") (pinfunction "G_1") (pintype "bidirectional"))
      (node (ref "R1PWRUSB") (pin "2") (pinfunction "2_2") (pintype "passive"))
    )
    (net (code "56") (name "unconnected-(IC1-NC-Pad4)") (class "Default")
      (node (ref "IC1") (pin "4") (pinfunction "NC_4") (pintype "no_connect"))
    )
    (net (code "57") (name "unconnected-(IC4-NC-Pad4)") (class "Default")
      (node (ref "IC4") (pin "4") (pinfunction "NC_4") (pintype "no_connect"))
    )
    (net (code "58") (name "unconnected-(J1-Pad1)") (class "Default")
      (node (ref "J1") (pin "1") (pinfunction "1_1") (pintype "bidirectional"))
    )
    (net (code "59") (name "unconnected-(J1-Pad6)") (class "Default")
      (node (ref "J1") (pin "6") (pinfunction "6_6") (pintype "bidirectional"))
    )
    (net (code "60") (name "unconnected-(J1-Pad7)") (class "Default")
      (node (ref "J1") (pin "7") (pinfunction "7_7") (pintype "bidirectional"))
    )
    (net (code "61") (name "unconnected-(J2-PadA8)") (class "Default")
      (node (ref "J2") (pin "A8") (pinfunction "A8_A8") (pintype "bidirectional"))
    )
    (net (code "62") (name "unconnected-(J2-PadB8)") (class "Default")
      (node (ref "J2") (pin "B8") (pinfunction "B8_B8") (pintype "bidirectional"))
    )
    (net (code "63") (name "unconnected-(J4-DAT1-PadP8)") (class "Default")
      (node (ref "J4") (pin "P8") (pinfunction "DAT1_P8") (pintype "bidirectional"))
    )
    (net (code "64") (name "unconnected-(J4-DAT2-PadP1)") (class "Default")
      (node (ref "J4") (pin "P1") (pinfunction "DAT2_P1") (pintype "bidirectional"))
    )
    (net (code "65") (name "unconnected-(J4-DETECTION_1-PadS1)") (class "Default")
      (node (ref "J4") (pin "S1") (pinfunction "DETECTION_1_S1") (pintype "bidirectional"))
    )
    (net (code "66") (name "unconnected-(J4-DETECTION_2-PadS2)") (class "Default")
      (node (ref "J4") (pin "S2") (pinfunction "DETECTION_2_S2") (pintype "bidirectional"))
    )
    (net (code "67") (name "unconnected-(U2-NC-Pad22)") (class "Default")
      (node (ref "U2") (pin "22") (pinfunction "NC_22") (pintype "no_connect"))
    )
    (net (code "68") (name "unconnected-(U4-~{ALERT}-Pad5)") (class "Default")
      (node (ref "U4") (pin "5") (pinfunction "~{ALERT}_5") (pintype "output"))
    )
  )
)
